# Cell_Balancing.net
KiCad netlist of a schematic drawn in Altium Designer
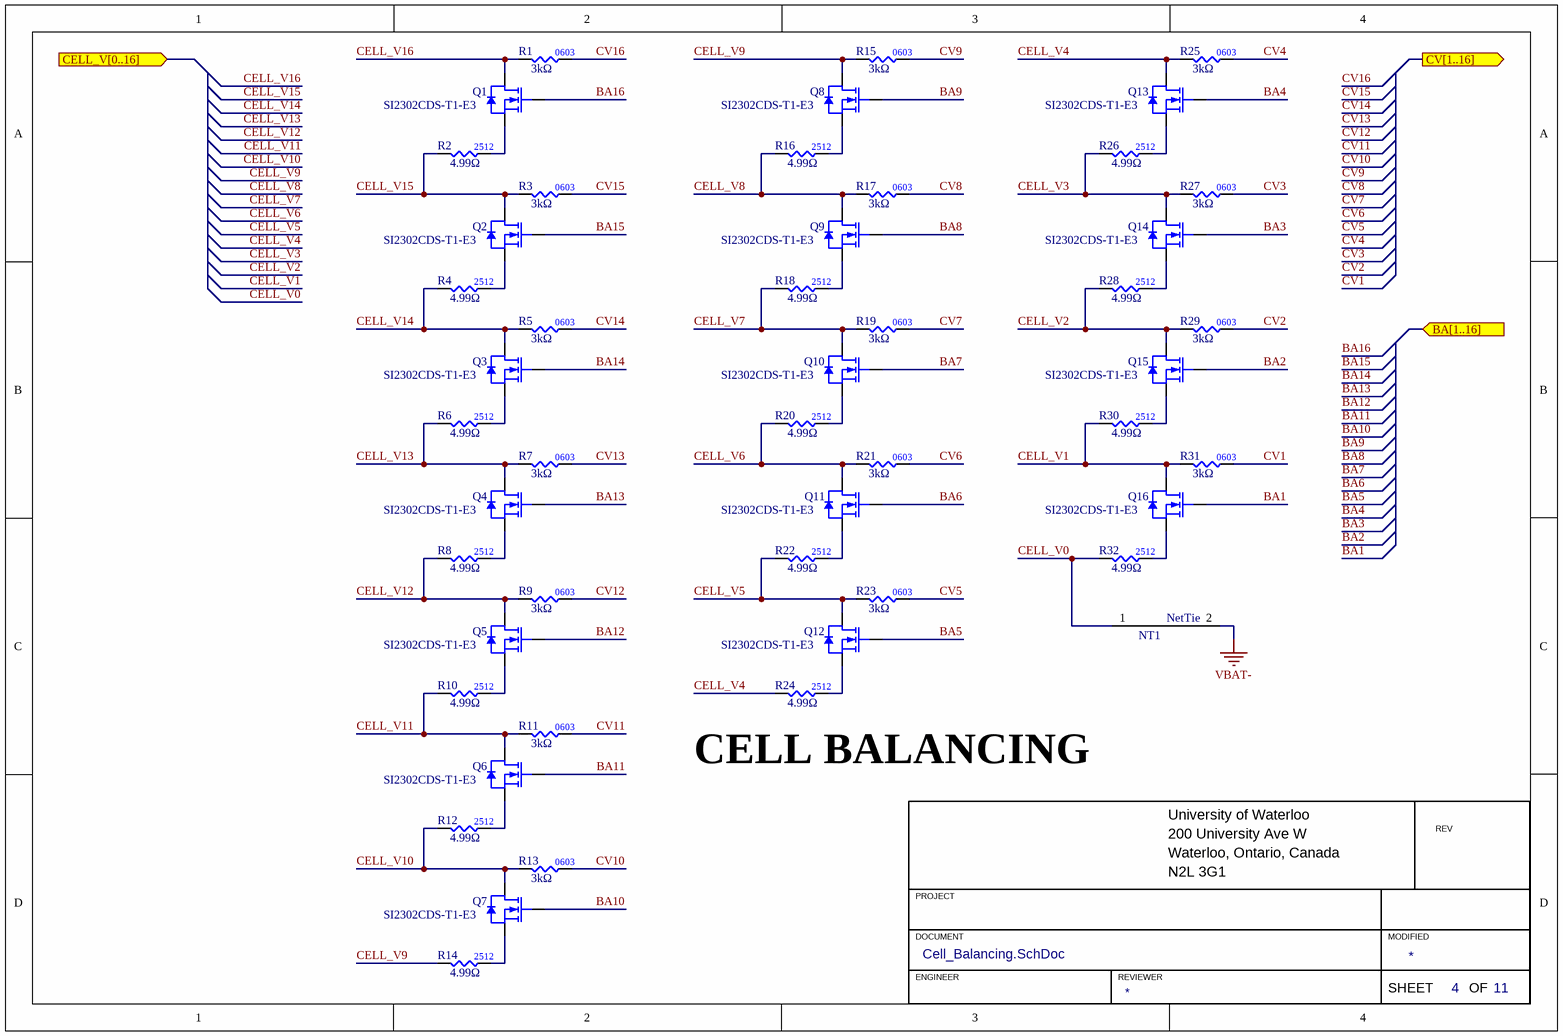
[diagram p0: Cell_Balancing.SchDoc]

(export (version "E")
  (design (tool "Eeschema 10.0.6"))
  (components
    (comp (ref "NT1")
      (value "NetTie")
      (footprint "NET_TIE")
      (libsource (lib "Personal_Schematic_Library_2022") (part "NetTie"))
    )
    (comp (ref "Q1")
      (value "NMOS_20V_6A")
      (footprint "SOT23-3")
      (description "MOSFET N-CH 20V 2.6A SOT23-3")
      (fields (field (name "MANUFACTURER PART NUMBER 1") "SI2302CDS-T1-E3"))
      (libsource (lib "Personal_Schematic_Library_2022") (part "NMOS_20V_2.6A"))
    )
    (comp (ref "Q2")
      (value "NMOS_20V_6A")
      (footprint "SOT23-3")
      (description "MOSFET N-CH 20V 2.6A SOT23-3")
      (fields (field (name "MANUFACTURER PART NUMBER 1") "SI2302CDS-T1-E3"))
      (libsource (lib "Personal_Schematic_Library_2022") (part "NMOS_20V_2.6A"))
    )
    (comp (ref "Q3")
      (value "NMOS_20V_6A")
      (footprint "SOT23-3")
      (description "MOSFET N-CH 20V 2.6A SOT23-3")
      (fields (field (name "MANUFACTURER PART NUMBER 1") "SI2302CDS-T1-E3"))
      (libsource (lib "Personal_Schematic_Library_2022") (part "NMOS_20V_2.6A"))
    )
    (comp (ref "Q4")
      (value "NMOS_20V_6A")
      (footprint "SOT23-3")
      (description "MOSFET N-CH 20V 2.6A SOT23-3")
      (fields (field (name "MANUFACTURER PART NUMBER 1") "SI2302CDS-T1-E3"))
      (libsource (lib "Personal_Schematic_Library_2022") (part "NMOS_20V_2.6A"))
    )
    (comp (ref "Q5")
      (value "NMOS_20V_6A")
      (footprint "SOT23-3")
      (description "MOSFET N-CH 20V 2.6A SOT23-3")
      (fields (field (name "MANUFACTURER PART NUMBER 1") "SI2302CDS-T1-E3"))
      (libsource (lib "Personal_Schematic_Library_2022") (part "NMOS_20V_2.6A"))
    )
    (comp (ref "Q6")
      (value "NMOS_20V_6A")
      (footprint "SOT23-3")
      (description "MOSFET N-CH 20V 2.6A SOT23-3")
      (fields (field (name "MANUFACTURER PART NUMBER 1") "SI2302CDS-T1-E3"))
      (libsource (lib "Personal_Schematic_Library_2022") (part "NMOS_20V_2.6A"))
    )
    (comp (ref "Q7")
      (value "NMOS_20V_6A")
      (footprint "SOT23-3")
      (description "MOSFET N-CH 20V 2.6A SOT23-3")
      (fields (field (name "MANUFACTURER PART NUMBER 1") "SI2302CDS-T1-E3"))
      (libsource (lib "Personal_Schematic_Library_2022") (part "NMOS_20V_2.6A"))
    )
    (comp (ref "Q8")
      (value "NMOS_20V_6A")
      (footprint "SOT23-3")
      (description "MOSFET N-CH 20V 2.6A SOT23-3")
      (fields (field (name "MANUFACTURER PART NUMBER 1") "SI2302CDS-T1-E3"))
      (libsource (lib "Personal_Schematic_Library_2022") (part "NMOS_20V_2.6A"))
    )
    (comp (ref "Q9")
      (value "NMOS_20V_6A")
      (footprint "SOT23-3")
      (description "MOSFET N-CH 20V 2.6A SOT23-3")
      (fields (field (name "MANUFACTURER PART NUMBER 1") "SI2302CDS-T1-E3"))
      (libsource (lib "Personal_Schematic_Library_2022") (part "NMOS_20V_2.6A"))
    )
    (comp (ref "Q10")
      (value "NMOS_20V_6A")
      (footprint "SOT23-3")
      (description "MOSFET N-CH 20V 2.6A SOT23-3")
      (fields (field (name "MANUFACTURER PART NUMBER 1") "SI2302CDS-T1-E3"))
      (libsource (lib "Personal_Schematic_Library_2022") (part "NMOS_20V_2.6A"))
    )
    (comp (ref "Q11")
      (value "NMOS_20V_6A")
      (footprint "SOT23-3")
      (description "MOSFET N-CH 20V 2.6A SOT23-3")
      (fields (field (name "MANUFACTURER PART NUMBER 1") "SI2302CDS-T1-E3"))
      (libsource (lib "Personal_Schematic_Library_2022") (part "NMOS_20V_2.6A"))
    )
    (comp (ref "Q12")
      (value "NMOS_20V_6A")
      (footprint "SOT23-3")
      (description "MOSFET N-CH 20V 2.6A SOT23-3")
      (fields (field (name "MANUFACTURER PART NUMBER 1") "SI2302CDS-T1-E3"))
      (libsource (lib "Personal_Schematic_Library_2022") (part "NMOS_20V_2.6A"))
    )
    (comp (ref "Q13")
      (value "NMOS_20V_6A")
      (footprint "SOT23-3")
      (description "MOSFET N-CH 20V 2.6A SOT23-3")
      (fields (field (name "MANUFACTURER PART NUMBER 1") "SI2302CDS-T1-E3"))
      (libsource (lib "Personal_Schematic_Library_2022") (part "NMOS_20V_2.6A"))
    )
    (comp (ref "Q14")
      (value "NMOS_20V_6A")
      (footprint "SOT23-3")
      (description "MOSFET N-CH 20V 2.6A SOT23-3")
      (fields (field (name "MANUFACTURER PART NUMBER 1") "SI2302CDS-T1-E3"))
      (libsource (lib "Personal_Schematic_Library_2022") (part "NMOS_20V_2.6A"))
    )
    (comp (ref "Q15")
      (value "NMOS_20V_6A")
      (footprint "SOT23-3")
      (description "MOSFET N-CH 20V 2.6A SOT23-3")
      (fields (field (name "MANUFACTURER PART NUMBER 1") "SI2302CDS-T1-E3"))
      (libsource (lib "Personal_Schematic_Library_2022") (part "NMOS_20V_2.6A"))
    )
    (comp (ref "Q16")
      (value "NMOS_20V_6A")
      (footprint "SOT23-3")
      (description "MOSFET N-CH 20V 2.6A SOT23-3")
      (fields (field (name "MANUFACTURER PART NUMBER 1") "SI2302CDS-T1-E3"))
      (libsource (lib "Personal_Schematic_Library_2022") (part "NMOS_20V_2.6A"))
    )
    (comp (ref "R1")
      (value "3kΩ")
      (footprint "RES0603")
      (description "RES 3K OHM 1% 1/10W 0603")
      (fields (field (name "Comment") "RES_3kΩ_0603_1%"))
      (libsource (lib "Personal_Schematic_Library_2022") (part "RES_3kΩ_0603_1%"))
    )
    (comp (ref "R2")
      (value "4.99Ω")
      (footprint "RES2512")
      (description "RES 4.99 OHM 1% 2W 2512")
      (fields (field (name "Comment") "RES_4.99Ω_2512_1%"))
      (libsource (lib "Personal_Schematic_Library_2022") (part "RES_4.99Ω_2512_1%"))
    )
    (comp (ref "R3")
      (value "3kΩ")
      (footprint "RES0603")
      (description "RES 3K OHM 1% 1/10W 0603")
      (fields (field (name "Comment") "RES_3kΩ_0603_1%"))
      (libsource (lib "Personal_Schematic_Library_2022") (part "RES_3kΩ_0603_1%"))
    )
    (comp (ref "R4")
      (value "4.99Ω")
      (footprint "RES2512")
      (description "RES 4.99 OHM 1% 2W 2512")
      (fields (field (name "Comment") "RES_4.99Ω_2512_1%"))
      (libsource (lib "Personal_Schematic_Library_2022") (part "RES_4.99Ω_2512_1%"))
    )
    (comp (ref "R5")
      (value "3kΩ")
      (footprint "RES0603")
      (description "RES 3K OHM 1% 1/10W 0603")
      (fields (field (name "Comment") "RES_3kΩ_0603_1%"))
      (libsource (lib "Personal_Schematic_Library_2022") (part "RES_3kΩ_0603_1%"))
    )
    (comp (ref "R6")
      (value "4.99Ω")
      (footprint "RES2512")
      (description "RES 4.99 OHM 1% 2W 2512")
      (fields (field (name "Comment") "RES_4.99Ω_2512_1%"))
      (libsource (lib "Personal_Schematic_Library_2022") (part "RES_4.99Ω_2512_1%"))
    )
    (comp (ref "R7")
      (value "3kΩ")
      (footprint "RES0603")
      (description "RES 3K OHM 1% 1/10W 0603")
      (fields (field (name "Comment") "RES_3kΩ_0603_1%"))
      (libsource (lib "Personal_Schematic_Library_2022") (part "RES_3kΩ_0603_1%"))
    )
    (comp (ref "R8")
      (value "4.99Ω")
      (footprint "RES2512")
      (description "RES 4.99 OHM 1% 2W 2512")
      (fields (field (name "Comment") "RES_4.99Ω_2512_1%"))
      (libsource (lib "Personal_Schematic_Library_2022") (part "RES_4.99Ω_2512_1%"))
    )
    (comp (ref "R9")
      (value "3kΩ")
      (footprint "RES0603")
      (description "RES 3K OHM 1% 1/10W 0603")
      (fields (field (name "Comment") "RES_3kΩ_0603_1%"))
      (libsource (lib "Personal_Schematic_Library_2022") (part "RES_3kΩ_0603_1%"))
    )
    (comp (ref "R10")
      (value "4.99Ω")
      (footprint "RES2512")
      (description "RES 4.99 OHM 1% 2W 2512")
      (fields (field (name "Comment") "RES_4.99Ω_2512_1%"))
      (libsource (lib "Personal_Schematic_Library_2022") (part "RES_4.99Ω_2512_1%"))
    )
    (comp (ref "R11")
      (value "3kΩ")
      (footprint "RES0603")
      (description "RES 3K OHM 1% 1/10W 0603")
      (fields (field (name "Comment") "RES_3kΩ_0603_1%"))
      (libsource (lib "Personal_Schematic_Library_2022") (part "RES_3kΩ_0603_1%"))
    )
    (comp (ref "R12")
      (value "4.99Ω")
      (footprint "RES2512")
      (description "RES 4.99 OHM 1% 2W 2512")
      (fields (field (name "Comment") "RES_4.99Ω_2512_1%"))
      (libsource (lib "Personal_Schematic_Library_2022") (part "RES_4.99Ω_2512_1%"))
    )
    (comp (ref "R13")
      (value "3kΩ")
      (footprint "RES0603")
      (description "RES 3K OHM 1% 1/10W 0603")
      (fields (field (name "Comment") "RES_3kΩ_0603_1%"))
      (libsource (lib "Personal_Schematic_Library_2022") (part "RES_3kΩ_0603_1%"))
    )
    (comp (ref "R14")
      (value "4.99Ω")
      (footprint "RES2512")
      (description "RES 4.99 OHM 1% 2W 2512")
      (fields (field (name "Comment") "RES_4.99Ω_2512_1%"))
      (libsource (lib "Personal_Schematic_Library_2022") (part "RES_4.99Ω_2512_1%"))
    )
    (comp (ref "R15")
      (value "3kΩ")
      (footprint "RES0603")
      (description "RES 3K OHM 1% 1/10W 0603")
      (fields (field (name "Comment") "RES_3kΩ_0603_1%"))
      (libsource (lib "Personal_Schematic_Library_2022") (part "RES_3kΩ_0603_1%"))
    )
    (comp (ref "R16")
      (value "4.99Ω")
      (footprint "RES2512")
      (description "RES 4.99 OHM 1% 2W 2512")
      (fields (field (name "Comment") "RES_4.99Ω_2512_1%"))
      (libsource (lib "Personal_Schematic_Library_2022") (part "RES_4.99Ω_2512_1%"))
    )
    (comp (ref "R17")
      (value "3kΩ")
      (footprint "RES0603")
      (description "RES 3K OHM 1% 1/10W 0603")
      (fields (field (name "Comment") "RES_3kΩ_0603_1%"))
      (libsource (lib "Personal_Schematic_Library_2022") (part "RES_3kΩ_0603_1%"))
    )
    (comp (ref "R18")
      (value "4.99Ω")
      (footprint "RES2512")
      (description "RES 4.99 OHM 1% 2W 2512")
      (fields (field (name "Comment") "RES_4.99Ω_2512_1%"))
      (libsource (lib "Personal_Schematic_Library_2022") (part "RES_4.99Ω_2512_1%"))
    )
    (comp (ref "R19")
      (value "3kΩ")
      (footprint "RES0603")
      (description "RES 3K OHM 1% 1/10W 0603")
      (fields (field (name "Comment") "RES_3kΩ_0603_1%"))
      (libsource (lib "Personal_Schematic_Library_2022") (part "RES_3kΩ_0603_1%"))
    )
    (comp (ref "R20")
      (value "4.99Ω")
      (footprint "RES2512")
      (description "RES 4.99 OHM 1% 2W 2512")
      (fields (field (name "Comment") "RES_4.99Ω_2512_1%"))
      (libsource (lib "Personal_Schematic_Library_2022") (part "RES_4.99Ω_2512_1%"))
    )
    (comp (ref "R21")
      (value "3kΩ")
      (footprint "RES0603")
      (description "RES 3K OHM 1% 1/10W 0603")
      (fields (field (name "Comment") "RES_3kΩ_0603_1%"))
      (libsource (lib "Personal_Schematic_Library_2022") (part "RES_3kΩ_0603_1%"))
    )
    (comp (ref "R22")
      (value "4.99Ω")
      (footprint "RES2512")
      (description "RES 4.99 OHM 1% 2W 2512")
      (fields (field (name "Comment") "RES_4.99Ω_2512_1%"))
      (libsource (lib "Personal_Schematic_Library_2022") (part "RES_4.99Ω_2512_1%"))
    )
    (comp (ref "R23")
      (value "3kΩ")
      (footprint "RES0603")
      (description "RES 3K OHM 1% 1/10W 0603")
      (fields (field (name "Comment") "RES_3kΩ_0603_1%"))
      (libsource (lib "Personal_Schematic_Library_2022") (part "RES_3kΩ_0603_1%"))
    )
    (comp (ref "R24")
      (value "4.99Ω")
      (footprint "RES2512")
      (description "RES 4.99 OHM 1% 2W 2512")
      (fields (field (name "Comment") "RES_4.99Ω_2512_1%"))
      (libsource (lib "Personal_Schematic_Library_2022") (part "RES_4.99Ω_2512_1%"))
    )
    (comp (ref "R25")
      (value "3kΩ")
      (footprint "RES0603")
      (description "RES 3K OHM 1% 1/10W 0603")
      (fields (field (name "Comment") "RES_3kΩ_0603_1%"))
      (libsource (lib "Personal_Schematic_Library_2022") (part "RES_3kΩ_0603_1%"))
    )
    (comp (ref "R26")
      (value "4.99Ω")
      (footprint "RES2512")
      (description "RES 4.99 OHM 1% 2W 2512")
      (fields (field (name "Comment") "RES_4.99Ω_2512_1%"))
      (libsource (lib "Personal_Schematic_Library_2022") (part "RES_4.99Ω_2512_1%"))
    )
    (comp (ref "R27")
      (value "3kΩ")
      (footprint "RES0603")
      (description "RES 3K OHM 1% 1/10W 0603")
      (fields (field (name "Comment") "RES_3kΩ_0603_1%"))
      (libsource (lib "Personal_Schematic_Library_2022") (part "RES_3kΩ_0603_1%"))
    )
    (comp (ref "R28")
      (value "4.99Ω")
      (footprint "RES2512")
      (description "RES 4.99 OHM 1% 2W 2512")
      (fields (field (name "Comment") "RES_4.99Ω_2512_1%"))
      (libsource (lib "Personal_Schematic_Library_2022") (part "RES_4.99Ω_2512_1%"))
    )
    (comp (ref "R29")
      (value "3kΩ")
      (footprint "RES0603")
      (description "RES 3K OHM 1% 1/10W 0603")
      (fields (field (name "Comment") "RES_3kΩ_0603_1%"))
      (libsource (lib "Personal_Schematic_Library_2022") (part "RES_3kΩ_0603_1%"))
    )
    (comp (ref "R30")
      (value "4.99Ω")
      (footprint "RES2512")
      (description "RES 4.99 OHM 1% 2W 2512")
      (fields (field (name "Comment") "RES_4.99Ω_2512_1%"))
      (libsource (lib "Personal_Schematic_Library_2022") (part "RES_4.99Ω_2512_1%"))
    )
    (comp (ref "R31")
      (value "3kΩ")
      (footprint "RES0603")
      (description "RES 3K OHM 1% 1/10W 0603")
      (fields (field (name "Comment") "RES_3kΩ_0603_1%"))
      (libsource (lib "Personal_Schematic_Library_2022") (part "RES_3kΩ_0603_1%"))
    )
    (comp (ref "R32")
      (value "4.99Ω")
      (footprint "RES2512")
      (description "RES 4.99 OHM 1% 2W 2512")
      (fields (field (name "Comment") "RES_4.99Ω_2512_1%"))
      (libsource (lib "Personal_Schematic_Library_2022") (part "RES_4.99Ω_2512_1%"))
    )
  )
  (nets
    (net (code "1") (name "/BA1") (class "Default")
      (node (ref "Q16") (pin "1") (pinfunction "GATE_1") (pintype "passive"))
    )
    (net (code "2") (name "/BA2") (class "Default")
      (node (ref "Q15") (pin "1") (pinfunction "GATE_1") (pintype "passive"))
    )
    (net (code "3") (name "/BA3") (class "Default")
      (node (ref "Q14") (pin "1") (pinfunction "GATE_1") (pintype "passive"))
    )
    (net (code "4") (name "/BA4") (class "Default")
      (node (ref "Q13") (pin "1") (pinfunction "GATE_1") (pintype "passive"))
    )
    (net (code "5") (name "/BA5") (class "Default")
      (node (ref "Q12") (pin "1") (pinfunction "GATE_1") (pintype "passive"))
    )
    (net (code "6") (name "/BA6") (class "Default")
      (node (ref "Q11") (pin "1") (pinfunction "GATE_1") (pintype "passive"))
    )
    (net (code "7") (name "/BA7") (class "Default")
      (node (ref "Q10") (pin "1") (pinfunction "GATE_1") (pintype "passive"))
    )
    (net (code "8") (name "/BA8") (class "Default")
      (node (ref "Q9") (pin "1") (pinfunction "GATE_1") (pintype "passive"))
    )
    (net (code "9") (name "/BA9") (class "Default")
      (node (ref "Q8") (pin "1") (pinfunction "GATE_1") (pintype "passive"))
    )
    (net (code "10") (name "/BA10") (class "Default")
      (node (ref "Q7") (pin "1") (pinfunction "GATE_1") (pintype "passive"))
    )
    (net (code "11") (name "/BA11") (class "Default")
      (node (ref "Q6") (pin "1") (pinfunction "GATE_1") (pintype "passive"))
    )
    (net (code "12") (name "/BA12") (class "Default")
      (node (ref "Q5") (pin "1") (pinfunction "GATE_1") (pintype "passive"))
    )
    (net (code "13") (name "/BA13") (class "Default")
      (node (ref "Q4") (pin "1") (pinfunction "GATE_1") (pintype "passive"))
    )
    (net (code "14") (name "/BA14") (class "Default")
      (node (ref "Q3") (pin "1") (pinfunction "GATE_1") (pintype "passive"))
    )
    (net (code "15") (name "/BA15") (class "Default")
      (node (ref "Q2") (pin "1") (pinfunction "GATE_1") (pintype "passive"))
    )
    (net (code "16") (name "/BA16") (class "Default")
      (node (ref "Q1") (pin "1") (pinfunction "GATE_1") (pintype "passive"))
    )
    (net (code "18") (name "/CELL_V0") (class "Default")
      (node (ref "NT1") (pin "1") (pinfunction "1_1") (pintype "passive"))
      (node (ref "R32") (pin "1") (pinfunction "1_1") (pintype "passive"))
    )
    (net (code "19") (name "/CELL_V1") (class "Default")
      (node (ref "Q16") (pin "3") (pinfunction "DRAIN_3") (pintype "passive"))
      (node (ref "R30") (pin "1") (pinfunction "1_1") (pintype "passive"))
      (node (ref "R31") (pin "1") (pinfunction "1_1") (pintype "passive"))
    )
    (net (code "20") (name "/CELL_V2") (class "Default")
      (node (ref "Q15") (pin "3") (pinfunction "DRAIN_3") (pintype "passive"))
      (node (ref "R28") (pin "1") (pinfunction "1_1") (pintype "passive"))
      (node (ref "R29") (pin "1") (pinfunction "1_1") (pintype "passive"))
    )
    (net (code "21") (name "/CELL_V3") (class "Default")
      (node (ref "Q14") (pin "3") (pinfunction "DRAIN_3") (pintype "passive"))
      (node (ref "R26") (pin "1") (pinfunction "1_1") (pintype "passive"))
      (node (ref "R27") (pin "1") (pinfunction "1_1") (pintype "passive"))
    )
    (net (code "22") (name "/CELL_V4") (class "Default")
      (node (ref "Q13") (pin "3") (pinfunction "DRAIN_3") (pintype "passive"))
      (node (ref "R24") (pin "1") (pinfunction "1_1") (pintype "passive"))
      (node (ref "R25") (pin "1") (pinfunction "1_1") (pintype "passive"))
    )
    (net (code "23") (name "/CELL_V5") (class "Default")
      (node (ref "Q12") (pin "3") (pinfunction "DRAIN_3") (pintype "passive"))
      (node (ref "R22") (pin "1") (pinfunction "1_1") (pintype "passive"))
      (node (ref "R23") (pin "1") (pinfunction "1_1") (pintype "passive"))
    )
    (net (code "24") (name "/CELL_V6") (class "Default")
      (node (ref "Q11") (pin "3") (pinfunction "DRAIN_3") (pintype "passive"))
      (node (ref "R20") (pin "1") (pinfunction "1_1") (pintype "passive"))
      (node (ref "R21") (pin "1") (pinfunction "1_1") (pintype "passive"))
    )
    (net (code "25") (name "/CELL_V7") (class "Default")
      (node (ref "Q10") (pin "3") (pinfunction "DRAIN_3") (pintype "passive"))
      (node (ref "R18") (pin "1") (pinfunction "1_1") (pintype "passive"))
      (node (ref "R19") (pin "1") (pinfunction "1_1") (pintype "passive"))
    )
    (net (code "26") (name "/CELL_V8") (class "Default")
      (node (ref "Q9") (pin "3") (pinfunction "DRAIN_3") (pintype "passive"))
      (node (ref "R16") (pin "1") (pinfunction "1_1") (pintype "passive"))
      (node (ref "R17") (pin "1") (pinfunction "1_1") (pintype "passive"))
    )
    (net (code "27") (name "/CELL_V9") (class "Default")
      (node (ref "Q8") (pin "3") (pinfunction "DRAIN_3") (pintype "passive"))
      (node (ref "R14") (pin "1") (pinfunction "1_1") (pintype "passive"))
      (node (ref "R15") (pin "1") (pinfunction "1_1") (pintype "passive"))
    )
    (net (code "28") (name "/CELL_V10") (class "Default")
      (node (ref "Q7") (pin "3") (pinfunction "DRAIN_3") (pintype "passive"))
      (node (ref "R12") (pin "1") (pinfunction "1_1") (pintype "passive"))
      (node (ref "R13") (pin "1") (pinfunction "1_1") (pintype "passive"))
    )
    (net (code "29") (name "/CELL_V11") (class "Default")
      (node (ref "Q6") (pin "3") (pinfunction "DRAIN_3") (pintype "passive"))
      (node (ref "R10") (pin "1") (pinfunction "1_1") (pintype "passive"))
      (node (ref "R11") (pin "1") (pinfunction "1_1") (pintype "passive"))
    )
    (net (code "30") (name "/CELL_V12") (class "Default")
      (node (ref "Q5") (pin "3") (pinfunction "DRAIN_3") (pintype "passive"))
      (node (ref "R8") (pin "1") (pinfunction "1_1") (pintype "passive"))
      (node (ref "R9") (pin "1") (pinfunction "1_1") (pintype "passive"))
    )
    (net (code "31") (name "/CELL_V13") (class "Default")
      (node (ref "Q4") (pin "3") (pinfunction "DRAIN_3") (pintype "passive"))
      (node (ref "R6") (pin "1") (pinfunction "1_1") (pintype "passive"))
      (node (ref "R7") (pin "1") (pinfunction "1_1") (pintype "passive"))
    )
    (net (code "32") (name "/CELL_V14") (class "Default")
      (node (ref "Q3") (pin "3") (pinfunction "DRAIN_3") (pintype "passive"))
      (node (ref "R4") (pin "1") (pinfunction "1_1") (pintype "passive"))
      (node (ref "R5") (pin "1") (pinfunction "1_1") (pintype "passive"))
    )
    (net (code "33") (name "/CELL_V15") (class "Default")
      (node (ref "Q2") (pin "3") (pinfunction "DRAIN_3") (pintype "passive"))
      (node (ref "R2") (pin "1") (pinfunction "1_1") (pintype "passive"))
      (node (ref "R3") (pin "1") (pinfunction "1_1") (pintype "passive"))
    )
    (net (code "34") (name "/CELL_V16") (class "Default")
      (node (ref "Q1") (pin "3") (pinfunction "DRAIN_3") (pintype "passive"))
      (node (ref "R1") (pin "1") (pinfunction "1_1") (pintype "passive"))
    )
    (net (code "36") (name "/CV1") (class "Default")
      (node (ref "R31") (pin "2") (pinfunction "2_2") (pintype "passive"))
    )
    (net (code "37") (name "/CV2") (class "Default")
      (node (ref "R29") (pin "2") (pinfunction "2_2") (pintype "passive"))
    )
    (net (code "38") (name "/CV3") (class "Default")
      (node (ref "R27") (pin "2") (pinfunction "2_2") (pintype "passive"))
    )
    (net (code "39") (name "/CV4") (class "Default")
      (node (ref "R25") (pin "2") (pinfunction "2_2") (pintype "passive"))
    )
    (net (code "40") (name "/CV5") (class "Default")
      (node (ref "R23") (pin "2") (pinfunction "2_2") (pintype "passive"))
    )
    (net (code "41") (name "/CV6") (class "Default")
      (node (ref "R21") (pin "2") (pinfunction "2_2") (pintype "passive"))
    )
    (net (code "42") (name "/CV7") (class "Default")
      (node (ref "R19") (pin "2") (pinfunction "2_2") (pintype "passive"))
    )
    (net (code "43") (name "/CV8") (class "Default")
      (node (ref "R17") (pin "2") (pinfunction "2_2") (pintype "passive"))
    )
    (net (code "44") (name "/CV9") (class "Default")
      (node (ref "R15") (pin "2") (pinfunction "2_2") (pintype "passive"))
    )
    (net (code "45") (name "/CV10") (class "Default")
      (node (ref "R13") (pin "2") (pinfunction "2_2") (pintype "passive"))
    )
    (net (code "46") (name "/CV11") (class "Default")
      (node (ref "R11") (pin "2") (pinfunction "2_2") (pintype "passive"))
    )
    (net (code "47") (name "/CV12") (class "Default")
      (node (ref "R9") (pin "2") (pinfunction "2_2") (pintype "passive"))
    )
    (net (code "48") (name "/CV13") (class "Default")
      (node (ref "R7") (pin "2") (pinfunction "2_2") (pintype "passive"))
    )
    (net (code "49") (name "/CV14") (class "Default")
      (node (ref "R5") (pin "2") (pinfunction "2_2") (pintype "passive"))
    )
    (net (code "50") (name "/CV15") (class "Default")
      (node (ref "R3") (pin "2") (pinfunction "2_2") (pintype "passive"))
    )
    (net (code "51") (name "/CV16") (class "Default")
      (node (ref "R1") (pin "2") (pinfunction "2_2") (pintype "passive"))
    )
    (net (code "53") (name "Net-(Q1-SOURCE)") (class "Default")
      (node (ref "Q1") (pin "2") (pinfunction "SOURCE_2") (pintype "passive"))
      (node (ref "R2") (pin "2") (pinfunction "2_2") (pintype "passive"))
    )
    (net (code "54") (name "Net-(Q2-SOURCE)") (class "Default")
      (node (ref "Q2") (pin "2") (pinfunction "SOURCE_2") (pintype "passive"))
      (node (ref "R4") (pin "2") (pinfunction "2_2") (pintype "passive"))
    )
    (net (code "55") (name "Net-(Q3-SOURCE)") (class "Default")
      (node (ref "Q3") (pin "2") (pinfunction "SOURCE_2") (pintype "passive"))
      (node (ref "R6") (pin "2") (pinfunction "2_2") (pintype "passive"))
    )
    (net (code "56") (name "Net-(Q4-SOURCE)") (class "Default")
      (node (ref "Q4") (pin "2") (pinfunction "SOURCE_2") (pintype "passive"))
      (node (ref "R8") (pin "2") (pinfunction "2_2") (pintype "passive"))
    )
    (net (code "57") (name "Net-(Q5-SOURCE)") (class "Default")
      (node (ref "Q5") (pin "2") (pinfunction "SOURCE_2") (pintype "passive"))
      (node (ref "R10") (pin "2") (pinfunction "2_2") (pintype "passive"))
    )
    (net (code "58") (name "Net-(Q6-SOURCE)") (class "Default")
      (node (ref "Q6") (pin "2") (pinfunction "SOURCE_2") (pintype "passive"))
      (node (ref "R12") (pin "2") (pinfunction "2_2") (pintype "passive"))
    )
    (net (code "59") (name "Net-(Q7-SOURCE)") (class "Default")
      (node (ref "Q7") (pin "2") (pinfunction "SOURCE_2") (pintype "passive"))
      (node (ref "R14") (pin "2") (pinfunction "2_2") (pintype "passive"))
    )
    (net (code "60") (name "Net-(Q8-SOURCE)") (class "Default")
      (node (ref "Q8") (pin "2") (pinfunction "SOURCE_2") (pintype "passive"))
      (node (ref "R16") (pin "2") (pinfunction "2_2") (pintype "passive"))
    )
    (net (code "61") (name "Net-(Q9-SOURCE)") (class "Default")
      (node (ref "Q9") (pin "2") (pinfunction "SOURCE_2") (pintype "passive"))
      (node (ref "R18") (pin "2") (pinfunction "2_2") (pintype "passive"))
    )
    (net (code "62") (name "Net-(Q10-SOURCE)") (class "Default")
      (node (ref "Q10") (pin "2") (pinfunction "SOURCE_2") (pintype "passive"))
      (node (ref "R20") (pin "2") (pinfunction "2_2") (pintype "passive"))
    )
    (net (code "63") (name "Net-(Q11-SOURCE)") (class "Default")
      (node (ref "Q11") (pin "2") (pinfunction "SOURCE_2") (pintype "passive"))
      (node (ref "R22") (pin "2") (pinfunction "2_2") (pintype "passive"))
    )
    (net (code "64") (name "Net-(Q12-SOURCE)") (class "Default")
      (node (ref "Q12") (pin "2") (pinfunction "SOURCE_2") (pintype "passive"))
      (node (ref "R24") (pin "2") (pinfunction "2_2") (pintype "passive"))
    )
    (net (code "65") (name "Net-(Q13-SOURCE)") (class "Default")
      (node (ref "Q13") (pin "2") (pinfunction "SOURCE_2") (pintype "passive"))
      (node (ref "R26") (pin "2") (pinfunction "2_2") (pintype "passive"))
    )
    (net (code "66") (name "Net-(Q14-SOURCE)") (class "Default")
      (node (ref "Q14") (pin "2") (pinfunction "SOURCE_2") (pintype "passive"))
      (node (ref "R28") (pin "2") (pinfunction "2_2") (pintype "passive"))
    )
    (net (code "67") (name "Net-(Q15-SOURCE)") (class "Default")
      (node (ref "Q15") (pin "2") (pinfunction "SOURCE_2") (pintype "passive"))
      (node (ref "R30") (pin "2") (pinfunction "2_2") (pintype "passive"))
    )
    (net (code "68") (name "Net-(Q16-SOURCE)") (class "Default")
      (node (ref "Q16") (pin "2") (pinfunction "SOURCE_2") (pintype "passive"))
      (node (ref "R32") (pin "2") (pinfunction "2_2") (pintype "passive"))
    )
    (net (code "69") (name "VBAT-") (class "Default")
      (node (ref "NT1") (pin "2") (pinfunction "2_2") (pintype "passive"))
    )
  )
)
